# 05_CPU_PWR.net
KiCad netlist of a schematic drawn in Altium Designer
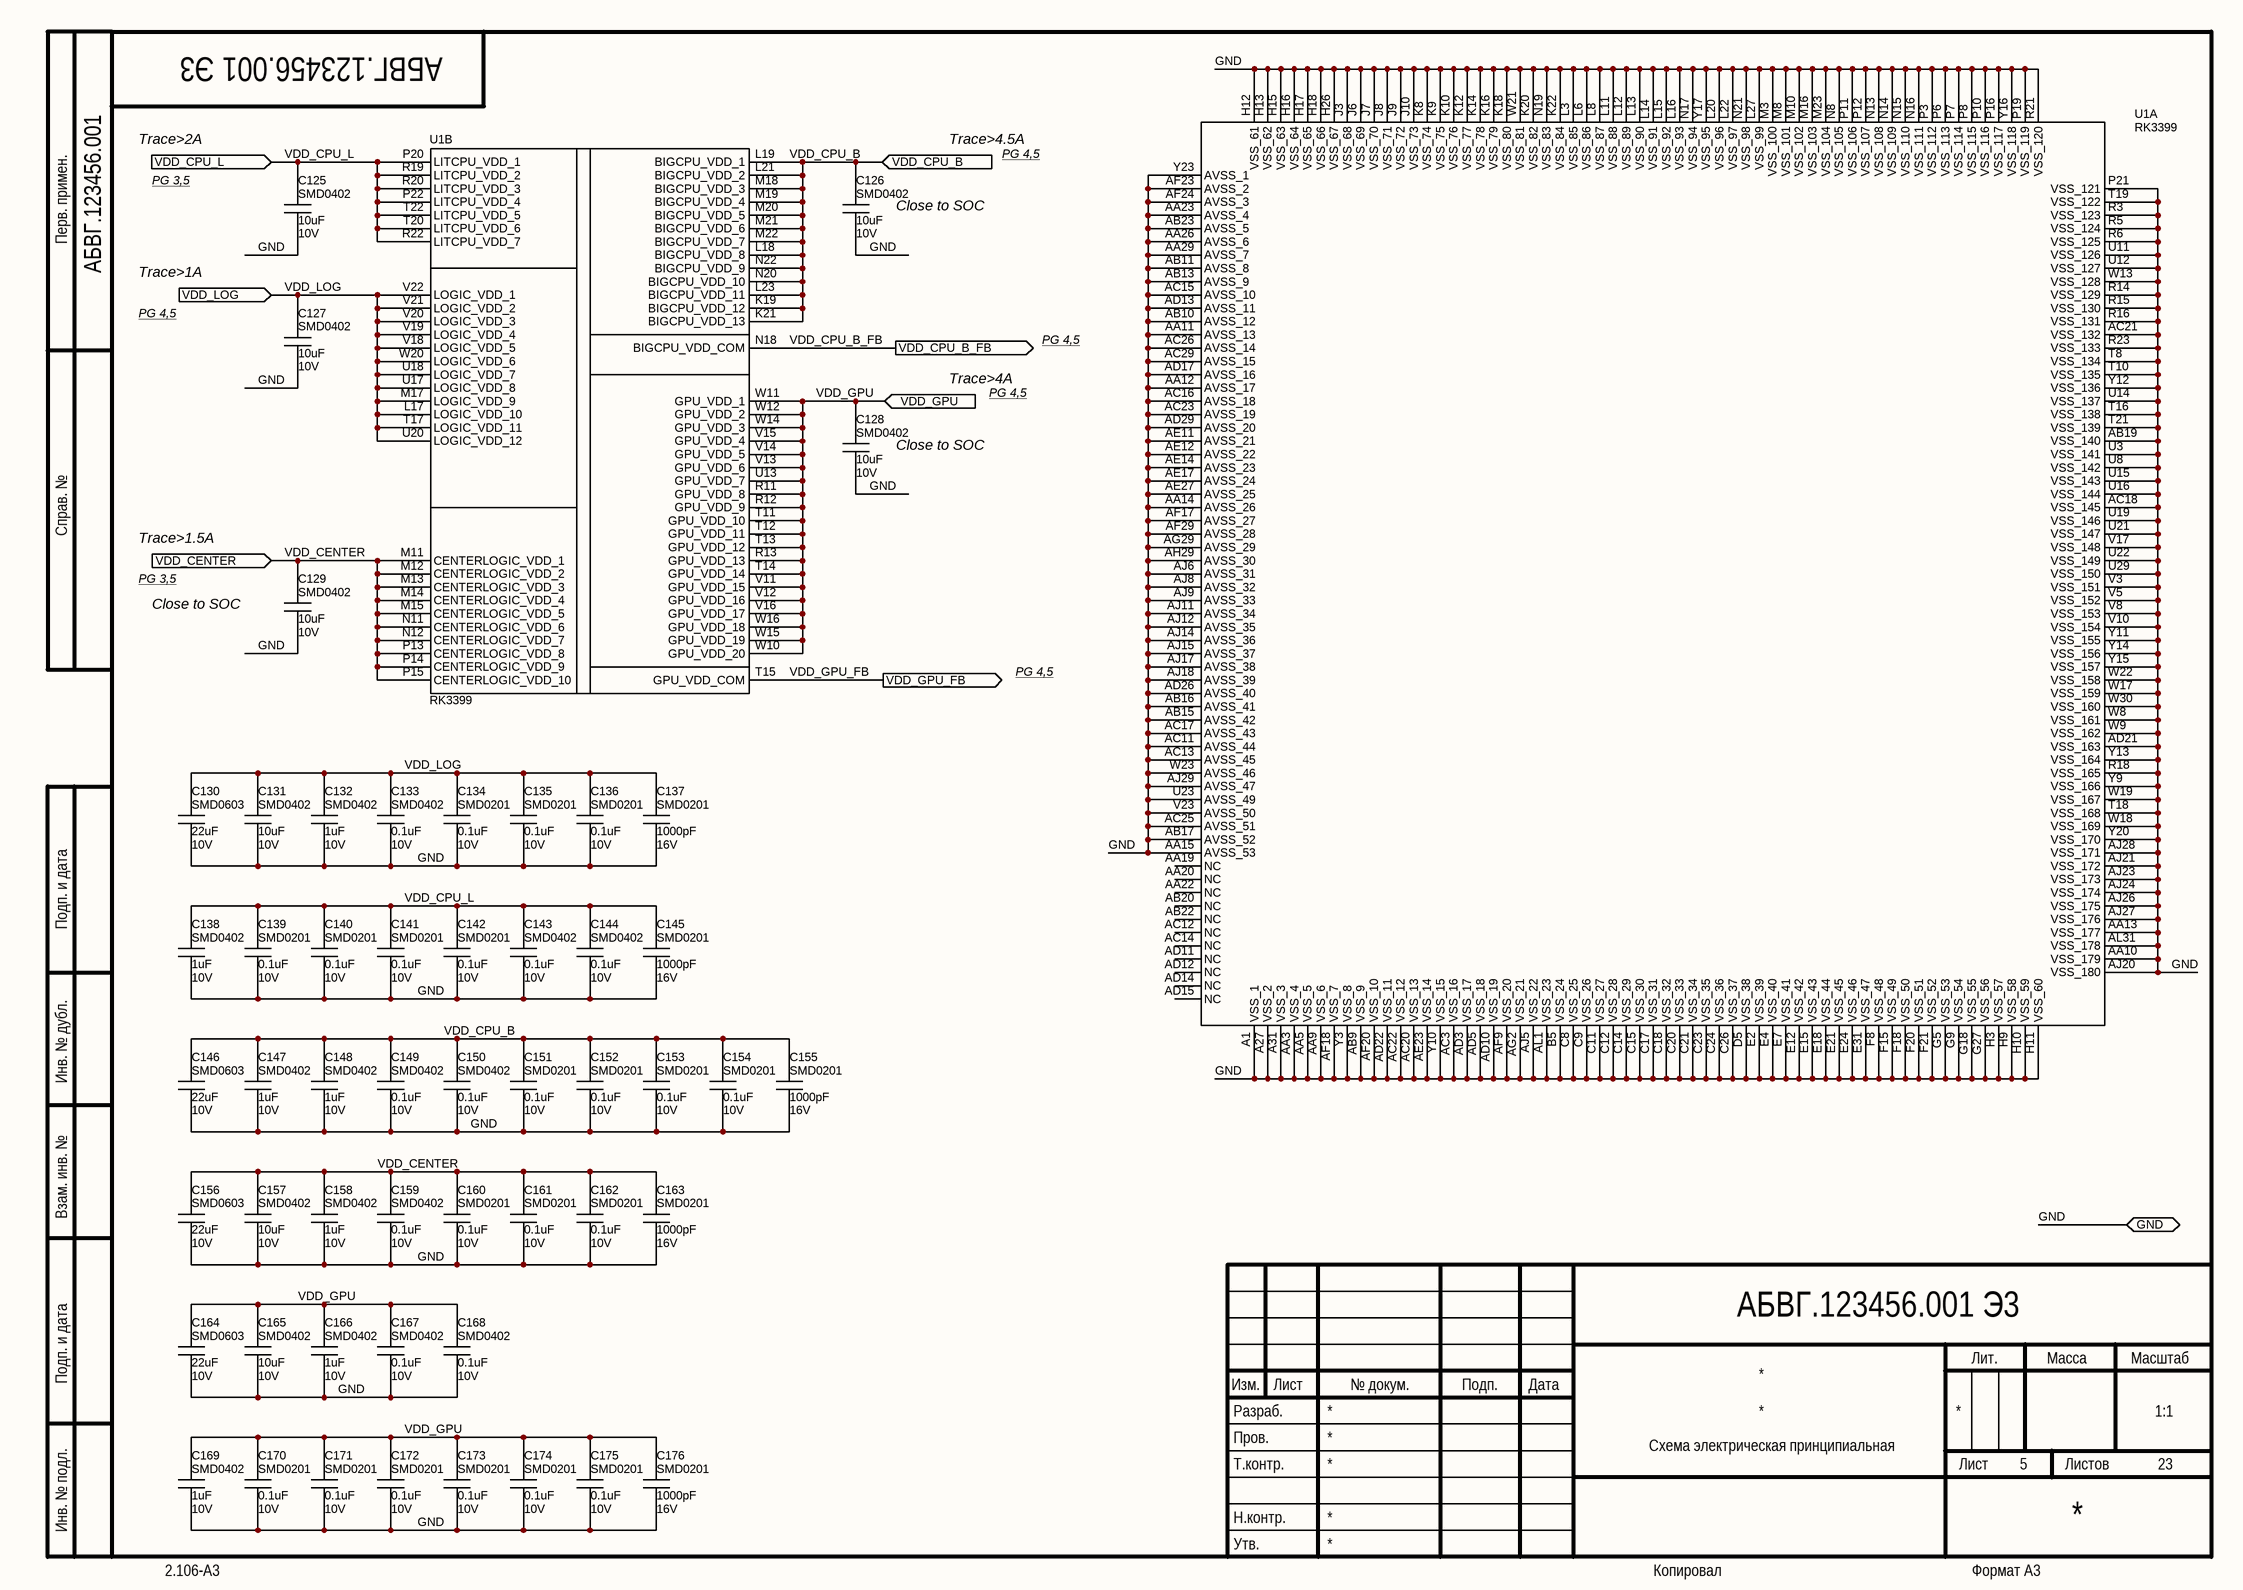
[diagram p0: 05 CPU_PWR.SchDoc]

(export (version "E")
  (design (tool "Eeschema 10.0.6"))
  (components
    (comp (ref "C125")
      (value "10uF")
      (footprint "Didur_PcbLib_1:CAP_SMD_0402_small")
      (fields
        (field (name "PACKAGE") "SMD0402")
        (field (name "PARTNUMBER") "CC0402MRX5R6BB106")
        (field (name "VOLTAGE") "10V")
      )
      (libsource (lib "Didur_SchLib_1") (part "Ceramic_Cap"))
    )
    (comp (ref "C126")
      (value "10uF")
      (footprint "Didur_PcbLib_1:CAP_SMD_0402")
      (fields
        (field (name "PACKAGE") "SMD0402")
        (field (name "PARTNUMBER") "CC0402MRX5R6BB106")
        (field (name "VOLTAGE") "10V")
      )
      (libsource (lib "Didur_SchLib_1") (part "Ceramic_Cap"))
    )
    (comp (ref "C127")
      (value "10uF")
      (footprint "Didur_PcbLib_1:CAP_SMD_0402_small")
      (fields
        (field (name "PACKAGE") "SMD0402")
        (field (name "PARTNUMBER") "CC0402MRX5R6BB106")
        (field (name "VOLTAGE") "10V")
      )
      (libsource (lib "Didur_SchLib_1") (part "Ceramic_Cap"))
    )
    (comp (ref "C128")
      (value "10uF")
      (footprint "Didur_PcbLib_1:CAP_SMD_0402_small")
      (fields
        (field (name "PACKAGE") "SMD0402")
        (field (name "PARTNUMBER") "CC0402MRX5R6BB106")
        (field (name "VOLTAGE") "10V")
      )
      (libsource (lib "Didur_SchLib_1") (part "Ceramic_Cap"))
    )
    (comp (ref "C129")
      (value "10uF")
      (footprint "Didur_PcbLib_1:CAP_SMD_0402")
      (fields
        (field (name "PACKAGE") "SMD0402")
        (field (name "PARTNUMBER") "CC0402MRX5R6BB106")
        (field (name "VOLTAGE") "10V")
      )
      (libsource (lib "Didur_SchLib_1") (part "Ceramic_Cap"))
    )
    (comp (ref "C130")
      (value "22uF")
      (footprint "CAP_SMD_0603")
      (fields
        (field (name "PACKAGE") "SMD0603")
        (field (name "PARTNUMBER") "CL10A226MP8NUNE")
        (field (name "VOLTAGE") "10V")
      )
      (libsource (lib "Didur_SchLib_1") (part "Ceramic_Cap"))
    )
    (comp (ref "C131")
      (value "10uF")
      (footprint "Didur_PcbLib_1:CAP_SMD_0402_small")
      (fields
        (field (name "PACKAGE") "SMD0402")
        (field (name "PARTNUMBER") "CC0402MRX5R6BB106")
        (field (name "VOLTAGE") "10V")
      )
      (libsource (lib "Didur_SchLib_1") (part "Ceramic_Cap"))
    )
    (comp (ref "C132")
      (value "1uF")
      (footprint "Didur_PcbLib_1:CAP_SMD_0402")
      (fields
        (field (name "PACKAGE") "SMD0402")
        (field (name "PARTNUMBER") "CC0402KRX5R6BB105")
        (field (name "VOLTAGE") "10V")
      )
      (libsource (lib "Didur_SchLib_1") (part "Ceramic_Cap"))
    )
    (comp (ref "C133")
      (value "0.1uF")
      (footprint "Didur_PcbLib_1:CAP_SMD_0402")
      (fields
        (field (name "PACKAGE") "SMD0402")
        (field (name "PARTNUMBER") "CC0402KRX5R6BB104")
        (field (name "VOLTAGE") "10V")
      )
      (libsource (lib "Didur_SchLib_1") (part "Ceramic_Cap"))
    )
    (comp (ref "C134")
      (value "0.1uF")
      (footprint "Didur_PcbLib_1:CAP_SMD_0201")
      (fields
        (field (name "PACKAGE") "SMD0201")
        (field (name "PARTNUMBER") "CC0201KRX5R6BB104")
        (field (name "VOLTAGE") "10V")
      )
      (libsource (lib "Didur_SchLib_1") (part "Ceramic_Cap"))
    )
    (comp (ref "C135")
      (value "0.1uF")
      (footprint "Didur_PcbLib_1:CAP_SMD_0201")
      (fields
        (field (name "PACKAGE") "SMD0201")
        (field (name "PARTNUMBER") "CC0201KRX5R6BB104")
        (field (name "VOLTAGE") "10V")
      )
      (libsource (lib "Didur_SchLib_1") (part "Ceramic_Cap"))
    )
    (comp (ref "C136")
      (value "0.1uF")
      (footprint "Didur_PcbLib_1:CAP_SMD_0201")
      (fields
        (field (name "PACKAGE") "SMD0201")
        (field (name "PARTNUMBER") "CC0201KRX5R6BB104")
        (field (name "VOLTAGE") "10V")
      )
      (libsource (lib "Didur_SchLib_1") (part "Ceramic_Cap"))
    )
    (comp (ref "C137")
      (value "1000pF")
      (footprint "Didur_PcbLib_1:CAP_SMD_0201")
      (fields
        (field (name "PACKAGE") "SMD0201")
        (field (name "PARTNUMBER") "CC0201KRX7R7BB102")
        (field (name "VOLTAGE") "16V")
      )
      (libsource (lib "Didur_SchLib_1") (part "Ceramic_Cap"))
    )
    (comp (ref "C138")
      (value "1uF")
      (footprint "Didur_PcbLib_1:CAP_SMD_0402")
      (fields
        (field (name "PACKAGE") "SMD0402")
        (field (name "PARTNUMBER") "CC0402KRX5R6BB105")
        (field (name "VOLTAGE") "10V")
      )
      (libsource (lib "Didur_SchLib_1") (part "Ceramic_Cap"))
    )
    (comp (ref "C139")
      (value "0.1uF")
      (footprint "Didur_PcbLib_1:CAP_SMD_0201")
      (fields
        (field (name "PACKAGE") "SMD0201")
        (field (name "PARTNUMBER") "CC0201KRX5R6BB104")
        (field (name "VOLTAGE") "10V")
      )
      (libsource (lib "Didur_SchLib_1") (part "Ceramic_Cap"))
    )
    (comp (ref "C140")
      (value "0.1uF")
      (footprint "Didur_PcbLib_1:CAP_SMD_0201")
      (fields
        (field (name "PACKAGE") "SMD0201")
        (field (name "PARTNUMBER") "CC0201KRX5R6BB104")
        (field (name "VOLTAGE") "10V")
      )
      (libsource (lib "Didur_SchLib_1") (part "Ceramic_Cap"))
    )
    (comp (ref "C141")
      (value "0.1uF")
      (footprint "Didur_PcbLib_1:CAP_SMD_0201")
      (fields
        (field (name "PACKAGE") "SMD0201")
        (field (name "PARTNUMBER") "CC0201KRX5R6BB104")
        (field (name "VOLTAGE") "10V")
      )
      (libsource (lib "Didur_SchLib_1") (part "Ceramic_Cap"))
    )
    (comp (ref "C142")
      (value "0.1uF")
      (footprint "Didur_PcbLib_1:CAP_SMD_0201")
      (fields
        (field (name "PACKAGE") "SMD0201")
        (field (name "PARTNUMBER") "CC0201KRX5R6BB104")
        (field (name "VOLTAGE") "10V")
      )
      (libsource (lib "Didur_SchLib_1") (part "Ceramic_Cap"))
    )
    (comp (ref "C143")
      (value "0.1uF")
      (footprint "Didur_PcbLib_1:CAP_SMD_0402")
      (fields
        (field (name "PACKAGE") "SMD0402")
        (field (name "PARTNUMBER") "CC0402KRX5R6BB104")
        (field (name "VOLTAGE") "10V")
      )
      (libsource (lib "Didur_SchLib_1") (part "Ceramic_Cap"))
    )
    (comp (ref "C144")
      (value "0.1uF")
      (footprint "Didur_PcbLib_1:CAP_SMD_0402")
      (fields
        (field (name "PACKAGE") "SMD0402")
        (field (name "PARTNUMBER") "CC0402KRX5R6BB104")
        (field (name "VOLTAGE") "10V")
      )
      (libsource (lib "Didur_SchLib_1") (part "Ceramic_Cap"))
    )
    (comp (ref "C145")
      (value "1000pF")
      (footprint "Didur_PcbLib_1:CAP_SMD_0201")
      (fields
        (field (name "PACKAGE") "SMD0201")
        (field (name "PARTNUMBER") "CC0201KRX7R7BB102")
        (field (name "VOLTAGE") "16V")
      )
      (libsource (lib "Didur_SchLib_1") (part "Ceramic_Cap"))
    )
    (comp (ref "C146")
      (value "22uF")
      (footprint "CAP_SMD_0603")
      (fields
        (field (name "PACKAGE") "SMD0603")
        (field (name "PARTNUMBER") "CL10A226MP8NUNE")
        (field (name "VOLTAGE") "10V")
      )
      (libsource (lib "Didur_SchLib_1") (part "Ceramic_Cap"))
    )
    (comp (ref "C147")
      (value "1uF")
      (footprint "Didur_PcbLib_1:CAP_SMD_0402")
      (fields
        (field (name "PACKAGE") "SMD0402")
        (field (name "PARTNUMBER") "CC0402KRX5R6BB105")
        (field (name "VOLTAGE") "10V")
      )
      (libsource (lib "Didur_SchLib_1") (part "Ceramic_Cap"))
    )
    (comp (ref "C148")
      (value "1uF")
      (footprint "Didur_PcbLib_1:CAP_SMD_0402_small")
      (fields
        (field (name "PACKAGE") "SMD0402")
        (field (name "PARTNUMBER") "CC0402KRX5R6BB105")
        (field (name "VOLTAGE") "10V")
      )
      (libsource (lib "Didur_SchLib_1") (part "Ceramic_Cap"))
    )
    (comp (ref "C149")
      (value "0.1uF")
      (footprint "Didur_PcbLib_1:CAP_SMD_0402")
      (fields
        (field (name "PACKAGE") "SMD0402")
        (field (name "PARTNUMBER") "CC0402KRX5R6BB104")
        (field (name "VOLTAGE") "10V")
      )
      (libsource (lib "Didur_SchLib_1") (part "Ceramic_Cap"))
    )
    (comp (ref "C150")
      (value "0.1uF")
      (footprint "Didur_PcbLib_1:CAP_SMD_0402")
      (fields
        (field (name "PACKAGE") "SMD0402")
        (field (name "PARTNUMBER") "CC0402KRX5R6BB104")
        (field (name "VOLTAGE") "10V")
      )
      (libsource (lib "Didur_SchLib_1") (part "Ceramic_Cap"))
    )
    (comp (ref "C151")
      (value "0.1uF")
      (footprint "Didur_PcbLib_1:CAP_SMD_0201")
      (fields
        (field (name "PACKAGE") "SMD0201")
        (field (name "PARTNUMBER") "CC0201KRX5R6BB104")
        (field (name "VOLTAGE") "10V")
      )
      (libsource (lib "Didur_SchLib_1") (part "Ceramic_Cap"))
    )
    (comp (ref "C152")
      (value "0.1uF")
      (footprint "Didur_PcbLib_1:CAP_SMD_0201")
      (fields
        (field (name "PACKAGE") "SMD0201")
        (field (name "PARTNUMBER") "CC0201KRX5R6BB104")
        (field (name "VOLTAGE") "10V")
      )
      (libsource (lib "Didur_SchLib_1") (part "Ceramic_Cap"))
    )
    (comp (ref "C153")
      (value "0.1uF")
      (footprint "Didur_PcbLib_1:CAP_SMD_0201")
      (fields
        (field (name "PACKAGE") "SMD0201")
        (field (name "PARTNUMBER") "CC0201KRX5R6BB104")
        (field (name "VOLTAGE") "10V")
      )
      (libsource (lib "Didur_SchLib_1") (part "Ceramic_Cap"))
    )
    (comp (ref "C154")
      (value "0.1uF")
      (footprint "Didur_PcbLib_1:CAP_SMD_0201")
      (fields
        (field (name "PACKAGE") "SMD0201")
        (field (name "PARTNUMBER") "CC0201KRX5R6BB104")
        (field (name "VOLTAGE") "10V")
      )
      (libsource (lib "Didur_SchLib_1") (part "Ceramic_Cap"))
    )
    (comp (ref "C155")
      (value "1000pF")
      (footprint "Didur_PcbLib_1:CAP_SMD_0201")
      (fields
        (field (name "PACKAGE") "SMD0201")
        (field (name "PARTNUMBER") "CC0201KRX7R7BB102")
        (field (name "VOLTAGE") "16V")
      )
      (libsource (lib "Didur_SchLib_1") (part "Ceramic_Cap"))
    )
    (comp (ref "C156")
      (value "22uF")
      (footprint "CAP_SMD_0603")
      (fields
        (field (name "PACKAGE") "SMD0603")
        (field (name "PARTNUMBER") "CL10A226MP8NUNE")
        (field (name "VOLTAGE") "10V")
      )
      (libsource (lib "Didur_SchLib_1") (part "Ceramic_Cap"))
    )
    (comp (ref "C157")
      (value "10uF")
      (footprint "Didur_PcbLib_1:CAP_SMD_0402_small")
      (fields
        (field (name "PACKAGE") "SMD0402")
        (field (name "PARTNUMBER") "CC0402MRX5R6BB106")
        (field (name "VOLTAGE") "10V")
      )
      (libsource (lib "Didur_SchLib_1") (part "Ceramic_Cap"))
    )
    (comp (ref "C158")
      (value "1uF")
      (footprint "Didur_PcbLib_1:CAP_SMD_0402_small")
      (fields
        (field (name "PACKAGE") "SMD0402")
        (field (name "PARTNUMBER") "CC0402KRX5R6BB105")
        (field (name "VOLTAGE") "10V")
      )
      (libsource (lib "Didur_SchLib_1") (part "Ceramic_Cap"))
    )
    (comp (ref "C159")
      (value "0.1uF")
      (footprint "Didur_PcbLib_1:CAP_SMD_0402")
      (fields
        (field (name "PACKAGE") "SMD0402")
        (field (name "PARTNUMBER") "CC0402KRX5R6BB104")
        (field (name "VOLTAGE") "10V")
      )
      (libsource (lib "Didur_SchLib_1") (part "Ceramic_Cap"))
    )
    (comp (ref "C160")
      (value "0.1uF")
      (footprint "Didur_PcbLib_1:CAP_SMD_0201")
      (fields
        (field (name "PACKAGE") "SMD0201")
        (field (name "PARTNUMBER") "CC0201KRX5R6BB104")
        (field (name "VOLTAGE") "10V")
      )
      (libsource (lib "Didur_SchLib_1") (part "Ceramic_Cap"))
    )
    (comp (ref "C161")
      (value "0.1uF")
      (footprint "Didur_PcbLib_1:CAP_SMD_0201")
      (fields
        (field (name "PACKAGE") "SMD0201")
        (field (name "PARTNUMBER") "CC0201KRX5R6BB104")
        (field (name "VOLTAGE") "10V")
      )
      (libsource (lib "Didur_SchLib_1") (part "Ceramic_Cap"))
    )
    (comp (ref "C162")
      (value "0.1uF")
      (footprint "Didur_PcbLib_1:CAP_SMD_0201")
      (fields
        (field (name "PACKAGE") "SMD0201")
        (field (name "PARTNUMBER") "CC0201KRX5R6BB104")
        (field (name "VOLTAGE") "10V")
      )
      (libsource (lib "Didur_SchLib_1") (part "Ceramic_Cap"))
    )
    (comp (ref "C163")
      (value "1000pF")
      (footprint "Didur_PcbLib_1:CAP_SMD_0201")
      (fields
        (field (name "PACKAGE") "SMD0201")
        (field (name "PARTNUMBER") "CC0201KRX7R7BB102")
        (field (name "VOLTAGE") "16V")
      )
      (libsource (lib "Didur_SchLib_1") (part "Ceramic_Cap"))
    )
    (comp (ref "C164")
      (value "22uF")
      (footprint "CAP_SMD_0603")
      (fields
        (field (name "PACKAGE") "SMD0603")
        (field (name "PARTNUMBER") "CL10A226MP8NUNE")
        (field (name "VOLTAGE") "10V")
      )
      (libsource (lib "Didur_SchLib_1") (part "Ceramic_Cap"))
    )
    (comp (ref "C165")
      (value "10uF")
      (footprint "Didur_PcbLib_1:CAP_SMD_0402")
      (fields
        (field (name "PACKAGE") "SMD0402")
        (field (name "PARTNUMBER") "CC0402MRX5R6BB106")
        (field (name "VOLTAGE") "10V")
      )
      (libsource (lib "Didur_SchLib_1") (part "Ceramic_Cap"))
    )
    (comp (ref "C166")
      (value "1uF")
      (footprint "Didur_PcbLib_1:CAP_SMD_0402")
      (fields
        (field (name "PACKAGE") "SMD0402")
        (field (name "PARTNUMBER") "CC0402KRX5R6BB105")
        (field (name "VOLTAGE") "10V")
      )
      (libsource (lib "Didur_SchLib_1") (part "Ceramic_Cap"))
    )
    (comp (ref "C167")
      (value "0.1uF")
      (footprint "Didur_PcbLib_1:CAP_SMD_0402")
      (fields
        (field (name "PACKAGE") "SMD0402")
        (field (name "PARTNUMBER") "CC0402KRX5R6BB104")
        (field (name "VOLTAGE") "10V")
      )
      (libsource (lib "Didur_SchLib_1") (part "Ceramic_Cap"))
    )
    (comp (ref "C168")
      (value "0.1uF")
      (footprint "Didur_PcbLib_1:CAP_SMD_0402")
      (fields
        (field (name "PACKAGE") "SMD0402")
        (field (name "PARTNUMBER") "CC0402KRX5R6BB104")
        (field (name "VOLTAGE") "10V")
      )
      (libsource (lib "Didur_SchLib_1") (part "Ceramic_Cap"))
    )
    (comp (ref "C169")
      (value "1uF")
      (footprint "Didur_PcbLib_1:CAP_SMD_0402_small")
      (fields
        (field (name "PACKAGE") "SMD0402")
        (field (name "PARTNUMBER") "CC0402KRX5R6BB105")
        (field (name "VOLTAGE") "10V")
      )
      (libsource (lib "Didur_SchLib_1") (part "Ceramic_Cap"))
    )
    (comp (ref "C170")
      (value "0.1uF")
      (footprint "Didur_PcbLib_1:CAP_SMD_0201")
      (fields
        (field (name "PACKAGE") "SMD0201")
        (field (name "PARTNUMBER") "CC0201KRX5R6BB104")
        (field (name "VOLTAGE") "10V")
      )
      (libsource (lib "Didur_SchLib_1") (part "Ceramic_Cap"))
    )
    (comp (ref "C171")
      (value "0.1uF")
      (footprint "Didur_PcbLib_1:CAP_SMD_0201")
      (fields
        (field (name "PACKAGE") "SMD0201")
        (field (name "PARTNUMBER") "CC0201KRX5R6BB104")
        (field (name "VOLTAGE") "10V")
      )
      (libsource (lib "Didur_SchLib_1") (part "Ceramic_Cap"))
    )
    (comp (ref "C172")
      (value "0.1uF")
      (footprint "Didur_PcbLib_1:CAP_SMD_0201")
      (fields
        (field (name "PACKAGE") "SMD0201")
        (field (name "PARTNUMBER") "CC0201KRX5R6BB104")
        (field (name "VOLTAGE") "10V")
      )
      (libsource (lib "Didur_SchLib_1") (part "Ceramic_Cap"))
    )
    (comp (ref "C173")
      (value "0.1uF")
      (footprint "Didur_PcbLib_1:CAP_SMD_0201")
      (fields
        (field (name "PACKAGE") "SMD0201")
        (field (name "PARTNUMBER") "CC0201KRX5R6BB104")
        (field (name "VOLTAGE") "10V")
      )
      (libsource (lib "Didur_SchLib_1") (part "Ceramic_Cap"))
    )
    (comp (ref "C174")
      (value "0.1uF")
      (footprint "Didur_PcbLib_1:CAP_SMD_0201")
      (fields
        (field (name "PACKAGE") "SMD0201")
        (field (name "PARTNUMBER") "CC0201KRX5R6BB104")
        (field (name "VOLTAGE") "10V")
      )
      (libsource (lib "Didur_SchLib_1") (part "Ceramic_Cap"))
    )
    (comp (ref "C175")
      (value "0.1uF")
      (footprint "Didur_PcbLib_1:CAP_SMD_0201")
      (fields
        (field (name "PACKAGE") "SMD0201")
        (field (name "PARTNUMBER") "CC0201KRX5R6BB104")
        (field (name "VOLTAGE") "10V")
      )
      (libsource (lib "Didur_SchLib_1") (part "Ceramic_Cap"))
    )
    (comp (ref "C176")
      (value "1000pF")
      (footprint "Didur_PcbLib_1:CAP_SMD_0201")
      (fields
        (field (name "PACKAGE") "SMD0201")
        (field (name "PARTNUMBER") "CC0201KRX7R7BB102")
        (field (name "VOLTAGE") "16V")
      )
      (libsource (lib "Didur_SchLib_1") (part "Ceramic_Cap"))
    )
    (comp (ref "U1")
      (value "RK3399")
      (footprint "BGA828C65P31X31_2100X2100X161N")
      (fields (field (name "Comment") "RK3399_FF"))
      (libsource (lib "Didur_SchLib_1") (part "RK3399_FF"))
    )
  )
  (nets
    (net (code "1") (name "/GND") (class "Default")
      (node (ref "C125") (pin "2") (pinfunction "2_2") (pintype "power_in"))
      (node (ref "C126") (pin "2") (pinfunction "2_2") (pintype "power_in"))
      (node (ref "C127") (pin "2") (pinfunction "2_2") (pintype "power_in"))
      (node (ref "C128") (pin "2") (pinfunction "2_2") (pintype "power_in"))
      (node (ref "C129") (pin "2") (pinfunction "2_2") (pintype "power_in"))
      (node (ref "C130") (pin "1") (pinfunction "1_1") (pintype "power_in"))
      (node (ref "C131") (pin "2") (pinfunction "2_2") (pintype "power_in"))
      (node (ref "C132") (pin "2") (pinfunction "2_2") (pintype "power_in"))
      (node (ref "C133") (pin "2") (pinfunction "2_2") (pintype "power_in"))
      (node (ref "C134") (pin "2") (pinfunction "2_2") (pintype "power_in"))
      (node (ref "C135") (pin "2") (pinfunction "2_2") (pintype "power_in"))
      (node (ref "C136") (pin "2") (pinfunction "2_2") (pintype "power_in"))
      (node (ref "C137") (pin "2") (pinfunction "2_2") (pintype "power_in"))
      (node (ref "C138") (pin "2") (pinfunction "2_2") (pintype "power_in"))
      (node (ref "C139") (pin "2") (pinfunction "2_2") (pintype "power_in"))
      (node (ref "C140") (pin "2") (pinfunction "2_2") (pintype "power_in"))
      (node (ref "C141") (pin "2") (pinfunction "2_2") (pintype "power_in"))
      (node (ref "C142") (pin "2") (pinfunction "2_2") (pintype "power_in"))
      (node (ref "C143") (pin "2") (pinfunction "2_2") (pintype "power_in"))
      (node (ref "C144") (pin "2") (pinfunction "2_2") (pintype "power_in"))
      (node (ref "C145") (pin "2") (pinfunction "2_2") (pintype "power_in"))
      (node (ref "C146") (pin "1") (pinfunction "1_1") (pintype "power_in"))
      (node (ref "C147") (pin "2") (pinfunction "2_2") (pintype "power_in"))
      (node (ref "C148") (pin "2") (pinfunction "2_2") (pintype "power_in"))
      (node (ref "C149") (pin "2") (pinfunction "2_2") (pintype "power_in"))
      (node (ref "C150") (pin "2") (pinfunction "2_2") (pintype "power_in"))
      (node (ref "C151") (pin "2") (pinfunction "2_2") (pintype "power_in"))
      (node (ref "C152") (pin "2") (pinfunction "2_2") (pintype "power_in"))
      (node (ref "C153") (pin "2") (pinfunction "2_2") (pintype "power_in"))
      (node (ref "C154") (pin "2") (pinfunction "2_2") (pintype "power_in"))
      (node (ref "C155") (pin "2") (pinfunction "2_2") (pintype "power_in"))
      (node (ref "C156") (pin "1") (pinfunction "1_1") (pintype "power_in"))
      (node (ref "C157") (pin "2") (pinfunction "2_2") (pintype "power_in"))
      (node (ref "C158") (pin "2") (pinfunction "2_2") (pintype "power_in"))
      (node (ref "C159") (pin "2") (pinfunction "2_2") (pintype "power_in"))
      (node (ref "C160") (pin "2") (pinfunction "2_2") (pintype "power_in"))
      (node (ref "C161") (pin "2") (pinfunction "2_2") (pintype "power_in"))
      (node (ref "C162") (pin "2") (pinfunction "2_2") (pintype "power_in"))
      (node (ref "C163") (pin "2") (pinfunction "2_2") (pintype "power_in"))
      (node (ref "C164") (pin "1") (pinfunction "1_1") (pintype "power_in"))
      (node (ref "C165") (pin "2") (pinfunction "2_2") (pintype "power_in"))
      (node (ref "C166") (pin "2") (pinfunction "2_2") (pintype "power_in"))
      (node (ref "C167") (pin "2") (pinfunction "2_2") (pintype "power_in"))
      (node (ref "C168") (pin "2") (pinfunction "2_2") (pintype "power_in"))
      (node (ref "C169") (pin "2") (pinfunction "2_2") (pintype "power_in"))
      (node (ref "C170") (pin "2") (pinfunction "2_2") (pintype "power_in"))
      (node (ref "C171") (pin "2") (pinfunction "2_2") (pintype "power_in"))
      (node (ref "C172") (pin "2") (pinfunction "2_2") (pintype "power_in"))
      (node (ref "C173") (pin "2") (pinfunction "2_2") (pintype "power_in"))
      (node (ref "C174") (pin "2") (pinfunction "2_2") (pintype "power_in"))
      (node (ref "C175") (pin "2") (pinfunction "2_2") (pintype "power_in"))
      (node (ref "C176") (pin "2") (pinfunction "2_2") (pintype "power_in"))
      (node (ref "U1") (pin "A1") (pinfunction "VSS_1_A1") (pintype "passive"))
      (node (ref "U1") (pin "A27") (pinfunction "VSS_2_A27") (pintype "passive"))
      (node (ref "U1") (pin "A31") (pinfunction "VSS_3_A31") (pintype "passive"))
      (node (ref "U1") (pin "AA10") (pinfunction "VSS_179_AA10") (pintype "power_in"))
      (node (ref "U1") (pin "AA11") (pinfunction "AVSS_13_AA11") (pintype "passive"))
      (node (ref "U1") (pin "AA12") (pinfunction "AVSS_17_AA12") (pintype "passive"))
      (node (ref "U1") (pin "AA13") (pinfunction "VSS_177_AA13") (pintype "power_in"))
      (node (ref "U1") (pin "AA14") (pinfunction "AVSS_26_AA14") (pintype "passive"))
      (node (ref "U1") (pin "AA15") (pinfunction "AVSS_53_AA15") (pintype "passive"))
      (node (ref "U1") (pin "AA23") (pinfunction "AVSS_4_AA23") (pintype "passive"))
      (node (ref "U1") (pin "AA26") (pinfunction "AVSS_6_AA26") (pintype "passive"))
      (node (ref "U1") (pin "AA29") (pinfunction "AVSS_7_AA29") (pintype "passive"))
      (node (ref "U1") (pin "AA3") (pinfunction "VSS_4_AA3") (pintype "passive"))
      (node (ref "U1") (pin "AA5") (pinfunction "VSS_5_AA5") (pintype "passive"))
      (node (ref "U1") (pin "AA9") (pinfunction "VSS_6_AA9") (pintype "passive"))
      (node (ref "U1") (pin "AB10") (pinfunction "AVSS_12_AB10") (pintype "passive"))
      (node (ref "U1") (pin "AB11") (pinfunction "AVSS_8_AB11") (pintype "passive"))
      (node (ref "U1") (pin "AB13") (pinfunction "AVSS_9_AB13") (pintype "passive"))
      (node (ref "U1") (pin "AB15") (pinfunction "AVSS_42_AB15") (pintype "passive"))
      (node (ref "U1") (pin "AB16") (pinfunction "AVSS_41_AB16") (pintype "passive"))
      (node (ref "U1") (pin "AB17") (pinfunction "AVSS_52_AB17") (pintype "passive"))
      (node (ref "U1") (pin "AB19") (pinfunction "VSS_140_AB19") (pintype "power_in"))
      (node (ref "U1") (pin "AB23") (pinfunction "AVSS_5_AB23") (pintype "passive"))
      (node (ref "U1") (pin "AB9") (pinfunction "VSS_9_AB9") (pintype "passive"))
      (node (ref "U1") (pin "AC11") (pinfunction "AVSS_44_AC11") (pintype "passive"))
      (node (ref "U1") (pin "AC13") (pinfunction "AVSS_45_AC13") (pintype "passive"))
      (node (ref "U1") (pin "AC15") (pinfunction "AVSS_10_AC15") (pintype "passive"))
      (node (ref "U1") (pin "AC16") (pinfunction "AVSS_18_AC16") (pintype "passive"))
      (node (ref "U1") (pin "AC17") (pinfunction "AVSS_43_AC17") (pintype "passive"))
      (node (ref "U1") (pin "AC18") (pinfunction "VSS_145_AC18") (pintype "power_in"))
      (node (ref "U1") (pin "AC20") (pinfunction "VSS_13_AC20") (pintype "passive"))
      (node (ref "U1") (pin "AC21") (pinfunction "VSS_132_AC21") (pintype "power_in"))
      (node (ref "U1") (pin "AC22") (pinfunction "VSS_12_AC22") (pintype "passive"))
      (node (ref "U1") (pin "AC23") (pinfunction "AVSS_19_AC23") (pintype "passive"))
      (node (ref "U1") (pin "AC25") (pinfunction "AVSS_51_AC25") (pintype "passive"))
      (node (ref "U1") (pin "AC26") (pinfunction "AVSS_14_AC26") (pintype "passive"))
      (node (ref "U1") (pin "AC29") (pinfunction "AVSS_15_AC29") (pintype "passive"))
      (node (ref "U1") (pin "AC3") (pinfunction "VSS_16_AC3") (pintype "passive"))
      (node (ref "U1") (pin "AD10") (pinfunction "VSS_19_AD10") (pintype "passive"))
      (node (ref "U1") (pin "AD13") (pinfunction "AVSS_11_AD13") (pintype "passive"))
      (node (ref "U1") (pin "AD17") (pinfunction "AVSS_16_AD17") (pintype "passive"))
      (node (ref "U1") (pin "AD21") (pinfunction "VSS_163_AD21") (pintype "power_in"))
      (node (ref "U1") (pin "AD22") (pinfunction "VSS_11_AD22") (pintype "passive"))
      (node (ref "U1") (pin "AD26") (pinfunction "AVSS_40_AD26") (pintype "passive"))
      (node (ref "U1") (pin "AD29") (pinfunction "AVSS_20_AD29") (pintype "passive"))
      (node (ref "U1") (pin "AD3") (pinfunction "VSS_17_AD3") (pintype "passive"))
      (node (ref "U1") (pin "AD5") (pinfunction "VSS_18_AD5") (pintype "passive"))
      (node (ref "U1") (pin "AE11") (pinfunction "AVSS_21_AE11") (pintype "passive"))
      (node (ref "U1") (pin "AE12") (pinfunction "AVSS_22_AE12") (pintype "passive"))
      (node (ref "U1") (pin "AE14") (pinfunction "AVSS_23_AE14") (pintype "passive"))
      (node (ref "U1") (pin "AE17") (pinfunction "AVSS_24_AE17") (pintype "passive"))
      (node (ref "U1") (pin "AE23") (pinfunction "VSS_14_AE23") (pintype "passive"))
      (node (ref "U1") (pin "AE27") (pinfunction "AVSS_25_AE27") (pintype "passive"))
      (node (ref "U1") (pin "AF17") (pinfunction "AVSS_27_AF17") (pintype "passive"))
      (node (ref "U1") (pin "AF18") (pinfunction "VSS_7_AF18") (pintype "passive"))
      (node (ref "U1") (pin "AF20") (pinfunction "VSS_10_AF20") (pintype "passive"))
      (node (ref "U1") (pin "AF23") (pinfunction "AVSS_2_AF23") (pintype "passive"))
      (node (ref "U1") (pin "AF24") (pinfunction "AVSS_3_AF24") (pintype "passive"))
      (node (ref "U1") (pin "AF29") (pinfunction "AVSS_28_AF29") (pintype "passive"))
      (node (ref "U1") (pin "AF9") (pinfunction "VSS_20_AF9") (pintype "passive"))
      (node (ref "U1") (pin "AG2") (pinfunction "VSS_21_AG2") (pintype "passive"))
      (node (ref "U1") (pin "AG29") (pinfunction "AVSS_29_AG29") (pintype "passive"))
      (node (ref "U1") (pin "AH29") (pinfunction "AVSS_30_AH29") (pintype "passive"))
      (node (ref "U1") (pin "AJ11") (pinfunction "AVSS_34_AJ11") (pintype "passive"))
      (node (ref "U1") (pin "AJ12") (pinfunction "AVSS_35_AJ12") (pintype "passive"))
      (node (ref "U1") (pin "AJ14") (pinfunction "AVSS_36_AJ14") (pintype "passive"))
      (node (ref "U1") (pin "AJ15") (pinfunction "AVSS_37_AJ15") (pintype "passive"))
      (node (ref "U1") (pin "AJ17") (pinfunction "AVSS_38_AJ17") (pintype "passive"))
      (node (ref "U1") (pin "AJ18") (pinfunction "AVSS_39_AJ18") (pintype "passive"))
      (node (ref "U1") (pin "AJ20") (pinfunction "VSS_180_AJ20") (pintype "power_in"))
      (node (ref "U1") (pin "AJ21") (pinfunction "VSS_172_AJ21") (pintype "power_in"))
      (node (ref "U1") (pin "AJ23") (pinfunction "VSS_173_AJ23") (pintype "power_in"))
      (node (ref "U1") (pin "AJ24") (pinfunction "VSS_174_AJ24") (pintype "power_in"))
      (node (ref "U1") (pin "AJ26") (pinfunction "VSS_175_AJ26") (pintype "power_in"))
      (node (ref "U1") (pin "AJ27") (pinfunction "VSS_176_AJ27") (pintype "power_in"))
      (node (ref "U1") (pin "AJ28") (pinfunction "VSS_171_AJ28") (pintype "power_in"))
      (node (ref "U1") (pin "AJ29") (pinfunction "AVSS_47_AJ29") (pintype "passive"))
      (node (ref "U1") (pin "AJ5") (pinfunction "VSS_22_AJ5") (pintype "passive"))
      (node (ref "U1") (pin "AJ6") (pinfunction "AVSS_31_AJ6") (pintype "passive"))
      (node (ref "U1") (pin "AJ8") (pinfunction "AVSS_32_AJ8") (pintype "passive"))
      (node (ref "U1") (pin "AJ9") (pinfunction "AVSS_33_AJ9") (pintype "passive"))
      (node (ref "U1") (pin "AL1") (pinfunction "VSS_23_AL1") (pintype "passive"))
      (node (ref "U1") (pin "AL31") (pinfunction "VSS_178_AL31") (pintype "power_in"))
      (node (ref "U1") (pin "B5") (pinfunction "VSS_24_B5") (pintype "passive"))
      (node (ref "U1") (pin "C11") (pinfunction "VSS_27_C11") (pintype "passive"))
      (node (ref "U1") (pin "C12") (pinfunction "VSS_28_C12") (pintype "passive"))
      (node (ref "U1") (pin "C14") (pinfunction "VSS_29_C14") (pintype "passive"))
      (node (ref "U1") (pin "C15") (pinfunction "VSS_30_C15") (pintype "passive"))
      (node (ref "U1") (pin "C17") (pinfunction "VSS_31_C17") (pintype "passive"))
      (node (ref "U1") (pin "C18") (pinfunction "VSS_32_C18") (pintype "passive"))
      (node (ref "U1") (pin "C20") (pinfunction "VSS_33_C20") (pintype "passive"))
      (node (ref "U1") (pin "C21") (pinfunction "VSS_34_C21") (pintype "passive"))
      (node (ref "U1") (pin "C23") (pinfunction "VSS_35_C23") (pintype "passive"))
      (node (ref "U1") (pin "C24") (pinfunction "VSS_36_C24") (pintype "passive"))
      (node (ref "U1") (pin "C26") (pinfunction "VSS_37_C26") (pintype "passive"))
      (node (ref "U1") (pin "C8") (pinfunction "VSS_25_C8") (pintype "passive"))
      (node (ref "U1") (pin "C9") (pinfunction "VSS_26_C9") (pintype "passive"))
      (node (ref "U1") (pin "D5") (pinfunction "VSS_38_D5") (pintype "passive"))
      (node (ref "U1") (pin "E12") (pinfunction "VSS_42_E12") (pintype "passive"))
      (node (ref "U1") (pin "E15") (pinfunction "VSS_43_E15") (pintype "passive"))
      (node (ref "U1") (pin "E18") (pinfunction "VSS_44_E18") (pintype "passive"))
      (node (ref "U1") (pin "E2") (pinfunction "VSS_39_E2") (pintype "passive"))
      (node (ref "U1") (pin "E21") (pinfunction "VSS_45_E21") (pintype "passive"))
      (node (ref "U1") (pin "E24") (pinfunction "VSS_46_E24") (pintype "passive"))
      (node (ref "U1") (pin "E31") (pinfunction "VSS_47_E31") (pintype "passive"))
      (node (ref "U1") (pin "E4") (pinfunction "VSS_40_E4") (pintype "passive"))
      (node (ref "U1") (pin "E7") (pinfunction "VSS_41_E7") (pintype "passive"))
      (node (ref "U1") (pin "F15") (pinfunction "VSS_49_F15") (pintype "passive"))
      (node (ref "U1") (pin "F18") (pinfunction "VSS_50_F18") (pintype "passive"))
      (node (ref "U1") (pin "F20") (pinfunction "VSS_51_F20") (pintype "passive"))
      (node (ref "U1") (pin "F21") (pinfunction "VSS_52_F21") (pintype "passive"))
      (node (ref "U1") (pin "F8") (pinfunction "VSS_48_F8") (pintype "passive"))
      (node (ref "U1") (pin "G18") (pinfunction "VSS_55_G18") (pintype "passive"))
      (node (ref "U1") (pin "G27") (pinfunction "VSS_56_G27") (pintype "passive"))
      (node (ref "U1") (pin "G5") (pinfunction "VSS_53_G5") (pintype "passive"))
      (node (ref "U1") (pin "G9") (pinfunction "VSS_54_G9") (pintype "passive"))
      (node (ref "U1") (pin "H10") (pinfunction "VSS_59_H10") (pintype "passive"))
      (node (ref "U1") (pin "H11") (pinfunction "VSS_60_H11") (pintype "passive"))
      (node (ref "U1") (pin "H12") (pinfunction "VSS_61_H12") (pintype "passive"))
      (node (ref "U1") (pin "H13") (pinfunction "VSS_62_H13") (pintype "passive"))
      (node (ref "U1") (pin "H15") (pinfunction "VSS_63_H15") (pintype "passive"))
      (node (ref "U1") (pin "H16") (pinfunction "VSS_64_H16") (pintype "passive"))
      (node (ref "U1") (pin "H17") (pinfunction "VSS_65_H17") (pintype "passive"))
      (node (ref "U1") (pin "H18") (pinfunction "VSS_66_H18") (pintype "passive"))
      (node (ref "U1") (pin "H26") (pinfunction "VSS_67_H26") (pintype "passive"))
      (node (ref "U1") (pin "H3") (pinfunction "VSS_57_H3") (pintype "passive"))
      (node (ref "U1") (pin "H9") (pinfunction "VSS_58_H9") (pintype "passive"))
      (node (ref "U1") (pin "J10") (pinfunction "VSS_73_J10") (pintype "passive"))
      (node (ref "U1") (pin "J3") (pinfunction "VSS_68_J3") (pintype "passive"))
      (node (ref "U1") (pin "J6") (pinfunction "VSS_69_J6") (pintype "passive"))
      (node (ref "U1") (pin "J7") (pinfunction "VSS_70_J7") (pintype "passive"))
      (node (ref "U1") (pin "J8") (pinfunction "VSS_71_J8") (pintype "passive"))
      (node (ref "U1") (pin "J9") (pinfunction "VSS_72_J9") (pintype "passive"))
      (node (ref "U1") (pin "K10") (pinfunction "VSS_76_K10") (pintype "passive"))
      (node (ref "U1") (pin "K12") (pinfunction "VSS_77_K12") (pintype "passive"))
      (node (ref "U1") (pin "K14") (pinfunction "VSS_78_K14") (pintype "passive"))
      (node (ref "U1") (pin "K16") (pinfunction "VSS_79_K16") (pintype "passive"))
      (node (ref "U1") (pin "K18") (pinfunction "VSS_80_K18") (pintype "passive"))
      (node (ref "U1") (pin "K20") (pinfunction "VSS_82_K20") (pintype "passive"))
      (node (ref "U1") (pin "K22") (pinfunction "VSS_84_K22") (pintype "passive"))
      (node (ref "U1") (pin "K8") (pinfunction "VSS_74_K8") (pintype "passive"))
      (node (ref "U1") (pin "K9") (pinfunction "VSS_75_K9") (pintype "passive"))
      (node (ref "U1") (pin "L11") (pinfunction "VSS_88_L11") (pintype "passive"))
      (node (ref "U1") (pin "L12") (pinfunction "VSS_89_L12") (pintype "passive"))
      (node (ref "U1") (pin "L13") (pinfunction "VSS_90_L13") (pintype "passive"))
      (node (ref "U1") (pin "L14") (pinfunction "VSS_91_L14") (pintype "power_in"))
      (node (ref "U1") (pin "L15") (pinfunction "VSS_92_L15") (pintype "power_in"))
      (node (ref "U1") (pin "L16") (pinfunction "VSS_93_L16") (pintype "power_in"))
      (node (ref "U1") (pin "L20") (pinfunction "VSS_96_L20") (pintype "power_in"))
      (node (ref "U1") (pin "L22") (pinfunction "VSS_97_L22") (pintype "power_in"))
      (node (ref "U1") (pin "L27") (pinfunction "VSS_99_L27") (pintype "power_in"))
      (node (ref "U1") (pin "L3") (pinfunction "VSS_85_L3") (pintype "passive"))
      (node (ref "U1") (pin "L6") (pinfunction "VSS_86_L6") (pintype "passive"))
      (node (ref "U1") (pin "L8") (pinfunction "VSS_87_L8") (pintype "passive"))
      (node (ref "U1") (pin "M10") (pinfunction "VSS_102_M10") (pintype "power_in"))
      (node (ref "U1") (pin "M16") (pinfunction "VSS_103_M16") (pintype "power_in"))
      (node (ref "U1") (pin "M23") (pinfunction "VSS_104_M23") (pintype "power_in"))
      (node (ref "U1") (pin "M3") (pinfunction "VSS_100_M3") (pintype "power_in"))
      (node (ref "U1") (pin "M8") (pinfunction "VSS_101_M8") (pintype "power_in"))
      (node (ref "U1") (pin "N13") (pinfunction "VSS_108_N13") (pintype "power_in"))
      (node (ref "U1") (pin "N14") (pinfunction "VSS_109_N14") (pintype "power_in"))
      (node (ref "U1") (pin "N15") (pinfunction "VSS_110_N15") (pintype "power_in"))
      (node (ref "U1") (pin "N16") (pinfunction "VSS_111_N16") (pintype "power_in"))
      (node (ref "U1") (pin "N17") (pinfunction "VSS_94_N17") (pintype "power_in"))
      (node (ref "U1") (pin "N19") (pinfunction "VSS_83_N19") (pintype "passive"))
      (node (ref "U1") (pin "N21") (pinfunction "VSS_98_N21") (pintype "power_in"))
      (node (ref "U1") (pin "N8") (pinfunction "VSS_105_N8") (pintype "power_in"))
      (node (ref "U1") (pin "P10") (pinfunction "VSS_116_P10") (pintype "power_in"))
      (node (ref "U1") (pin "P11") (pinfunction "VSS_106_P11") (pintype "power_in"))
      (node (ref "U1") (pin "P12") (pinfunction "VSS_107_P12") (pintype "power_in"))
      (node (ref "U1") (pin "P16") (pinfunction "VSS_117_P16") (pintype "power_in"))
      (node (ref "U1") (pin "P19") (pinfunction "VSS_119_P19") (pintype "power_in"))
      (node (ref "U1") (pin "P21") (pinfunction "VSS_121_P21") (pintype "power_in"))
      (node (ref "U1") (pin "P3") (pinfunction "VSS_112_P3") (pintype "power_in"))
      (node (ref "U1") (pin "P6") (pinfunction "VSS_113_P6") (pintype "power_in"))
      (node (ref "U1") (pin "P7") (pinfunction "VSS_114_P7") (pintype "power_in"))
      (node (ref "U1") (pin "P8") (pinfunction "VSS_115_P8") (pintype "power_in"))
      (node (ref "U1") (pin "R14") (pinfunction "VSS_129_R14") (pintype "power_in"))
      (node (ref "U1") (pin "R15") (pinfunction "VSS_130_R15") (pintype "power_in"))
      (node (ref "U1") (pin "R16") (pinfunction "VSS_131_R16") (pintype "power_in"))
      (node (ref "U1") (pin "R18") (pinfunction "VSS_165_R18") (pintype "power_in"))
      (node (ref "U1") (pin "R21") (pinfunction "VSS_120_R21") (pintype "power_in"))
      (node (ref "U1") (pin "R23") (pinfunction "VSS_133_R23") (pintype "power_in"))
      (node (ref "U1") (pin "R3") (pinfunction "VSS_123_R3") (pintype "power_in"))
      (node (ref "U1") (pin "R5") (pinfunction "VSS_124_R5") (pintype "power_in"))
      (node (ref "U1") (pin "R6") (pinfunction "VSS_125_R6") (pintype "power_in"))
      (node (ref "U1") (pin "T10") (pinfunction "VSS_135_T10") (pintype "power_in"))
      (node (ref "U1") (pin "T16") (pinfunction "VSS_138_T16") (pintype "power_in"))
      (node (ref "U1") (pin "T18") (pinfunction "VSS_168_T18") (pintype "power_in"))
      (node (ref "U1") (pin "T19") (pinfunction "VSS_122_T19") (pintype "power_in"))
      (node (ref "U1") (pin "T21") (pinfunction "VSS_139_T21") (pintype "power_in"))
      (node (ref "U1") (pin "T8") (pinfunction "VSS_134_T8") (pintype "power_in"))
      (node (ref "U1") (pin "U11") (pinfunction "VSS_126_U11") (pintype "power_in"))
      (node (ref "U1") (pin "U12") (pinfunction "VSS_127_U12") (pintype "power_in"))
      (node (ref "U1") (pin "U14") (pinfunction "VSS_137_U14") (pintype "power_in"))
      (node (ref "U1") (pin "U15") (pinfunction "VSS_143_U15") (pintype "power_in"))
      (node (ref "U1") (pin "U16") (pinfunction "VSS_144_U16") (pintype "power_in"))
      (node (ref "U1") (pin "U19") (pinfunction "VSS_146_U19") (pintype "power_in"))
      (node (ref "U1") (pin "U21") (pinfunction "VSS_147_U21") (pintype "power_in"))
      (node (ref "U1") (pin "U22") (pinfunction "VSS_149_U22") (pintype "power_in"))
      (node (ref "U1") (pin "U23") (pinfunction "AVSS_49_U23") (pintype "passive"))
      (node (ref "U1") (pin "U29") (pinfunction "VSS_150_U29") (pintype "power_in"))
      (node (ref "U1") (pin "U3") (pinfunction "VSS_141_U3") (pintype "power_in"))
      (node (ref "U1") (pin "U8") (pinfunction "VSS_142_U8") (pintype "power_in"))
      (node (ref "U1") (pin "V10") (pinfunction "VSS_154_V10") (pintype "power_in"))
      (node (ref "U1") (pin "V17") (pinfunction "VSS_148_V17") (pintype "power_in"))
      (node (ref "U1") (pin "V23") (pinfunction "AVSS_50_V23") (pintype "passive"))
      (node (ref "U1") (pin "V3") (pinfunction "VSS_151_V3") (pintype "power_in"))
      (node (ref "U1") (pin "V5") (pinfunction "VSS_152_V5") (pintype "power_in"))
      (node (ref "U1") (pin "V8") (pinfunction "VSS_153_V8") (pintype "power_in"))
      (node (ref "U1") (pin "W13") (pinfunction "VSS_128_W13") (pintype "power_in"))
      (node (ref "U1") (pin "W17") (pinfunction "VSS_159_W17") (pintype "power_in"))
      (node (ref "U1") (pin "W18") (pinfunction "VSS_169_W18") (pintype "power_in"))
      (node (ref "U1") (pin "W19") (pinfunction "VSS_167_W19") (pintype "power_in"))
      (node (ref "U1") (pin "W21") (pinfunction "VSS_81_W21") (pintype "passive"))
      (node (ref "U1") (pin "W22") (pinfunction "VSS_158_W22") (pintype "power_in"))
      (node (ref "U1") (pin "W23") (pinfunction "AVSS_46_W23") (pintype "passive"))
      (node (ref "U1") (pin "W30") (pinfunction "VSS_160_W30") (pintype "power_in"))
      (node (ref "U1") (pin "W8") (pinfunction "VSS_161_W8") (pintype "power_in"))
      (node (ref "U1") (pin "W9") (pinfunction "VSS_162_W9") (pintype "power_in"))
      (node (ref "U1") (pin "Y10") (pinfunction "VSS_15_Y10") (pintype "passive"))
      (node (ref "U1") (pin "Y11") (pinfunction "VSS_155_Y11") (pintype "power_in"))
      (node (ref "U1") (pin "Y12") (pinfunction "VSS_136_Y12") (pintype "power_in"))
      (node (ref "U1") (pin "Y13") (pinfunction "VSS_164_Y13") (pintype "power_in"))
      (node (ref "U1") (pin "Y14") (pinfunction "VSS_156_Y14") (pintype "power_in"))
      (node (ref "U1") (pin "Y15") (pinfunction "VSS_157_Y15") (pintype "power_in"))
      (node (ref "U1") (pin "Y16") (pinfunction "VSS_118_Y16") (pintype "power_in"))
      (node (ref "U1") (pin "Y17") (pinfunction "VSS_95_Y17") (pintype "power_in"))
      (node (ref "U1") (pin "Y20") (pinfunction "VSS_170_Y20") (pintype "power_in"))
      (node (ref "U1") (pin "Y23") (pinfunction "AVSS_1_Y23") (pintype "passive"))
      (node (ref "U1") (pin "Y3") (pinfunction "VSS_8_Y3") (pintype "passive"))
      (node (ref "U1") (pin "Y9") (pinfunction "VSS_166_Y9") (pintype "power_in"))
    )
    (net (code "2") (name "/VDD_CENTER") (class "Default")
      (node (ref "C129") (pin "1") (pinfunction "1_1") (pintype "power_in"))
      (node (ref "C156") (pin "2") (pinfunction "2_2") (pintype "power_in"))
      (node (ref "C157") (pin "1") (pinfunction "1_1") (pintype "power_in"))
      (node (ref "C158") (pin "1") (pinfunction "1_1") (pintype "power_in"))
      (node (ref "C159") (pin "1") (pinfunction "1_1") (pintype "power_in"))
      (node (ref "C160") (pin "1") (pinfunction "1_1") (pintype "power_in"))
      (node (ref "C161") (pin "1") (pinfunction "1_1") (pintype "power_in"))
      (node (ref "C162") (pin "1") (pinfunction "1_1") (pintype "power_in"))
      (node (ref "C163") (pin "1") (pinfunction "1_1") (pintype "power_in"))
      (node (ref "U1") (pin "M11") (pinfunction "CENTERLOGIC_VDD_1_M11") (pintype "passive"))
      (node (ref "U1") (pin "M12") (pinfunction "CENTERLOGIC_VDD_2_M12") (pintype "passive"))
      (node (ref "U1") (pin "M13") (pinfunction "CENTERLOGIC_VDD_3_M13") (pintype "passive"))
      (node (ref "U1") (pin "M14") (pinfunction "CENTERLOGIC_VDD_4_M14") (pintype "passive"))
      (node (ref "U1") (pin "M15") (pinfunction "CENTERLOGIC_VDD_5_M15") (pintype "passive"))
      (node (ref "U1") (pin "N11") (pinfunction "CENTERLOGIC_VDD_6_N11") (pintype "passive"))
      (node (ref "U1") (pin "N12") (pinfunction "CENTERLOGIC_VDD_7_N12") (pintype "passive"))
      (node (ref "U1") (pin "P13") (pinfunction "CENTERLOGIC_VDD_8_P13") (pintype "passive"))
      (node (ref "U1") (pin "P14") (pinfunction "CENTERLOGIC_VDD_9_P14") (pintype "passive"))
      (node (ref "U1") (pin "P15") (pinfunction "CENTERLOGIC_VDD_10_P15") (pintype "passive"))
    )
    (net (code "3") (name "/VDD_CPU_B") (class "Default")
      (node (ref "C126") (pin "1") (pinfunction "1_1") (pintype "power_in"))
      (node (ref "C146") (pin "2") (pinfunction "2_2") (pintype "power_in"))
      (node (ref "C147") (pin "1") (pinfunction "1_1") (pintype "power_in"))
      (node (ref "C148") (pin "1") (pinfunction "1_1") (pintype "power_in"))
      (node (ref "C149") (pin "1") (pinfunction "1_1") (pintype "power_in"))
      (node (ref "C150") (pin "1") (pinfunction "1_1") (pintype "power_in"))
      (node (ref "C151") (pin "1") (pinfunction "1_1") (pintype "power_in"))
      (node (ref "C152") (pin "1") (pinfunction "1_1") (pintype "power_in"))
      (node (ref "C153") (pin "1") (pinfunction "1_1") (pintype "power_in"))
      (node (ref "C154") (pin "1") (pinfunction "1_1") (pintype "power_in"))
      (node (ref "C155") (pin "1") (pinfunction "1_1") (pintype "power_in"))
      (node (ref "U1") (pin "K19") (pinfunction "BIGCPU_VDD_12_K19") (pintype "passive"))
      (node (ref "U1") (pin "K21") (pinfunction "BIGCPU_VDD_13_K21") (pintype "passive"))
      (node (ref "U1") (pin "L18") (pinfunction "BIGCPU_VDD_8_L18") (pintype "passive"))
      (node (ref "U1") (pin "L19") (pinfunction "BIGCPU_VDD_1_L19") (pintype "passive"))
      (node (ref "U1") (pin "L21") (pinfunction "BIGCPU_VDD_2_L21") (pintype "passive"))
      (node (ref "U1") (pin "L23") (pinfunction "BIGCPU_VDD_11_L23") (pintype "passive"))
      (node (ref "U1") (pin "M18") (pinfunction "BIGCPU_VDD_3_M18") (pintype "passive"))
      (node (ref "U1") (pin "M19") (pinfunction "BIGCPU_VDD_4_M19") (pintype "passive"))
      (node (ref "U1") (pin "M20") (pinfunction "BIGCPU_VDD_5_M20") (pintype "passive"))
      (node (ref "U1") (pin "M21") (pinfunction "BIGCPU_VDD_6_M21") (pintype "passive"))
      (node (ref "U1") (pin "M22") (pinfunction "BIGCPU_VDD_7_M22") (pintype "passive"))
      (node (ref "U1") (pin "N20") (pinfunction "BIGCPU_VDD_10_N20") (pintype "passive"))
      (node (ref "U1") (pin "N22") (pinfunction "BIGCPU_VDD_9_N22") (pintype "passive"))
    )
    (net (code "4") (name "/VDD_CPU_B_FB") (class "Default")
      (node (ref "U1") (pin "N18") (pinfunction "BIGCPU_VDD_COM_N18") (pintype "passive"))
    )
    (net (code "5") (name "/VDD_CPU_L") (class "Default")
      (node (ref "C125") (pin "1") (pinfunction "1_1") (pintype "power_in"))
      (node (ref "C138") (pin "1") (pinfunction "1_1") (pintype "power_in"))
      (node (ref "C139") (pin "1") (pinfunction "1_1") (pintype "power_in"))
      (node (ref "C140") (pin "1") (pinfunction "1_1") (pintype "power_in"))
      (node (ref "C141") (pin "1") (pinfunction "1_1") (pintype "power_in"))
      (node (ref "C142") (pin "1") (pinfunction "1_1") (pintype "power_in"))
      (node (ref "C143") (pin "1") (pinfunction "1_1") (pintype "power_in"))
      (node (ref "C144") (pin "1") (pinfunction "1_1") (pintype "power_in"))
      (node (ref "C145") (pin "1") (pinfunction "1_1") (pintype "power_in"))
      (node (ref "U1") (pin "P20") (pinfunction "LITCPU_VDD_1_P20") (pintype "passive"))
      (node (ref "U1") (pin "P22") (pinfunction "LITCPU_VDD_4_P22") (pintype "passive"))
      (node (ref "U1") (pin "R19") (pinfunction "LITCPU_VDD_2_R19") (pintype "passive"))
      (node (ref "U1") (pin "R20") (pinfunction "LITCPU_VDD_3_R20") (pintype "passive"))
      (node (ref "U1") (pin "R22") (pinfunction "LITCPU_VDD_7_R22") (pintype "passive"))
      (node (ref "U1") (pin "T20") (pinfunction "LITCPU_VDD_6_T20") (pintype "passive"))
      (node (ref "U1") (pin "T22") (pinfunction "LITCPU_VDD_5_T22") (pintype "passive"))
    )
    (net (code "6") (name "/VDD_GPU") (class "Default")
      (node (ref "C128") (pin "1") (pinfunction "1_1") (pintype "power_in"))
      (node (ref "C164") (pin "2") (pinfunction "2_2") (pintype "power_in"))
      (node (ref "C165") (pin "1") (pinfunction "1_1") (pintype "power_in"))
      (node (ref "C166") (pin "1") (pinfunction "1_1") (pintype "power_in"))
      (node (ref "C167") (pin "1") (pinfunction "1_1") (pintype "power_in"))
      (node (ref "C168") (pin "1") (pinfunction "1_1") (pintype "power_in"))
      (node (ref "C169") (pin "1") (pinfunction "1_1") (pintype "power_in"))
      (node (ref "C170") (pin "1") (pinfunction "1_1") (pintype "power_in"))
      (node (ref "C171") (pin "1") (pinfunction "1_1") (pintype "power_in"))
      (node (ref "C172") (pin "1") (pinfunction "1_1") (pintype "power_in"))
      (node (ref "C173") (pin "1") (pinfunction "1_1") (pintype "power_in"))
      (node (ref "C174") (pin "1") (pinfunction "1_1") (pintype "power_in"))
      (node (ref "C175") (pin "1") (pinfunction "1_1") (pintype "power_in"))
      (node (ref "C176") (pin "1") (pinfunction "1_1") (pintype "power_in"))
      (node (ref "U1") (pin "R11") (pinfunction "GPU_VDD_8_R11") (pintype "passive"))
      (node (ref "U1") (pin "R12") (pinfunction "GPU_VDD_9_R12") (pintype "passive"))
      (node (ref "U1") (pin "R13") (pinfunction "GPU_VDD_13_R13") (pintype "passive"))
      (node (ref "U1") (pin "T11") (pinfunction "GPU_VDD_10_T11") (pintype "passive"))
      (node (ref "U1") (pin "T12") (pinfunction "GPU_VDD_11_T12") (pintype "passive"))
      (node (ref "U1") (pin "T13") (pinfunction "GPU_VDD_12_T13") (pintype "passive"))
      (node (ref "U1") (pin "T14") (pinfunction "GPU_VDD_14_T14") (pintype "passive"))
      (node (ref "U1") (pin "U13") (pinfunction "GPU_VDD_7_U13") (pintype "passive"))
      (node (ref "U1") (pin "V11") (pinfunction "GPU_VDD_15_V11") (pintype "passive"))
      (node (ref "U1") (pin "V12") (pinfunction "GPU_VDD_16_V12") (pintype "passive"))
      (node (ref "U1") (pin "V13") (pinfunction "GPU_VDD_6_V13") (pintype "passive"))
      (node (ref "U1") (pin "V14") (pinfunction "GPU_VDD_5_V14") (pintype "passive"))
      (node (ref "U1") (pin "V15") (pinfunction "GPU_VDD_4_V15") (pintype "passive"))
      (node (ref "U1") (pin "V16") (pinfunction "GPU_VDD_17_V16") (pintype "passive"))
      (node (ref "U1") (pin "W10") (pinfunction "GPU_VDD_20_W10") (pintype "passive"))
      (node (ref "U1") (pin "W11") (pinfunction "GPU_VDD_1_W11") (pintype "passive"))
      (node (ref "U1") (pin "W12") (pinfunction "GPU_VDD_2_W12") (pintype "passive"))
      (node (ref "U1") (pin "W14") (pinfunction "GPU_VDD_3_W14") (pintype "passive"))
      (node (ref "U1") (pin "W15") (pinfunction "GPU_VDD_19_W15") (pintype "passive"))
      (node (ref "U1") (pin "W16") (pinfunction "GPU_VDD_18_W16") (pintype "passive"))
    )
    (net (code "7") (name "/VDD_GPU_FB") (class "Default")
      (node (ref "U1") (pin "T15") (pinfunction "GPU_VDD_COM_T15") (pintype "passive"))
    )
    (net (code "8") (name "/VDD_LOG") (class "Default")
      (node (ref "C127") (pin "1") (pinfunction "1_1") (pintype "power_in"))
      (node (ref "C130") (pin "2") (pinfunction "2_2") (pintype "power_in"))
      (node (ref "C131") (pin "1") (pinfunction "1_1") (pintype "power_in"))
      (node (ref "C132") (pin "1") (pinfunction "1_1") (pintype "power_in"))
      (node (ref "C133") (pin "1") (pinfunction "1_1") (pintype "power_in"))
      (node (ref "C134") (pin "1") (pinfunction "1_1") (pintype "power_in"))
      (node (ref "C135") (pin "1") (pinfunction "1_1") (pintype "power_in"))
      (node (ref "C136") (pin "1") (pinfunction "1_1") (pintype "power_in"))
      (node (ref "C137") (pin "1") (pinfunction "1_1") (pintype "power_in"))
      (node (ref "U1") (pin "L17") (pinfunction "LOGIC_VDD_10_L17") (pintype "passive"))
      (node (ref "U1") (pin "M17") (pinfunction "LOGIC_VDD_9_M17") (pintype "passive"))
      (node (ref "U1") (pin "T17") (pinfunction "LOGIC_VDD_11_T17") (pintype "passive"))
      (node (ref "U1") (pin "U17") (pinfunction "LOGIC_VDD_8_U17") (pintype "passive"))
      (node (ref "U1") (pin "U18") (pinfunction "LOGIC_VDD_7_U18") (pintype "passive"))
      (node (ref "U1") (pin "U20") (pinfunction "LOGIC_VDD_12_U20") (pintype "passive"))
      (node (ref "U1") (pin "V18") (pinfunction "LOGIC_VDD_5_V18") (pintype "passive"))
      (node (ref "U1") (pin "V19") (pinfunction "LOGIC_VDD_4_V19") (pintype "passive"))
      (node (ref "U1") (pin "V20") (pinfunction "LOGIC_VDD_3_V20") (pintype "passive"))
      (node (ref "U1") (pin "V21") (pinfunction "LOGIC_VDD_2_V21") (pintype "passive"))
      (node (ref "U1") (pin "V22") (pinfunction "LOGIC_VDD_1_V22") (pintype "passive"))
      (node (ref "U1") (pin "W20") (pinfunction "LOGIC_VDD_6_W20") (pintype "passive"))
    )
    (net (code "9") (name "unconnected-(U1A-NC-PadAA19)") (class "Default")
      (node (ref "U1") (pin "AA19") (pinfunction "NC_AA19") (pintype "passive"))
    )
    (net (code "10") (name "unconnected-(U1A-NC-PadAA20)") (class "Default")
      (node (ref "U1") (pin "AA20") (pinfunction "NC_AA20") (pintype "passive"))
    )
    (net (code "11") (name "unconnected-(U1A-NC-PadAA22)") (class "Default")
      (node (ref "U1") (pin "AA22") (pinfunction "NC_AA22") (pintype "passive"))
    )
    (net (code "12") (name "unconnected-(U1A-NC-PadAB20)") (class "Default")
      (node (ref "U1") (pin "AB20") (pinfunction "NC_AB20") (pintype "passive"))
    )
    (net (code "13") (name "unconnected-(U1A-NC-PadAB22)") (class "Default")
      (node (ref "U1") (pin "AB22") (pinfunction "NC_AB22") (pintype "passive"))
    )
    (net (code "14") (name "unconnected-(U1A-NC-PadAC12)") (class "Default")
      (node (ref "U1") (pin "AC12") (pinfunction "NC_AC12") (pintype "passive"))
    )
    (net (code "15") (name "unconnected-(U1A-NC-PadAC14)") (class "Default")
      (node (ref "U1") (pin "AC14") (pinfunction "NC_AC14") (pintype "passive"))
    )
    (net (code "16") (name "unconnected-(U1A-NC-PadAD11)") (class "Default")
      (node (ref "U1") (pin "AD11") (pinfunction "NC_AD11") (pintype "passive"))
    )
    (net (code "17") (name "unconnected-(U1A-NC-PadAD12)") (class "Default")
      (node (ref "U1") (pin "AD12") (pinfunction "NC_AD12") (pintype "passive"))
    )
    (net (code "18") (name "unconnected-(U1A-NC-PadAD14)") (class "Default")
      (node (ref "U1") (pin "AD14") (pinfunction "NC_AD14") (pintype "passive"))
    )
    (net (code "19") (name "unconnected-(U1A-NC-PadAD15)") (class "Default")
      (node (ref "U1") (pin "AD15") (pinfunction "NC_AD15") (pintype "passive"))
    )
  )
)
